# ESP32_S2_solo.net
KiCad netlist of a schematic drawn in Altium Designer
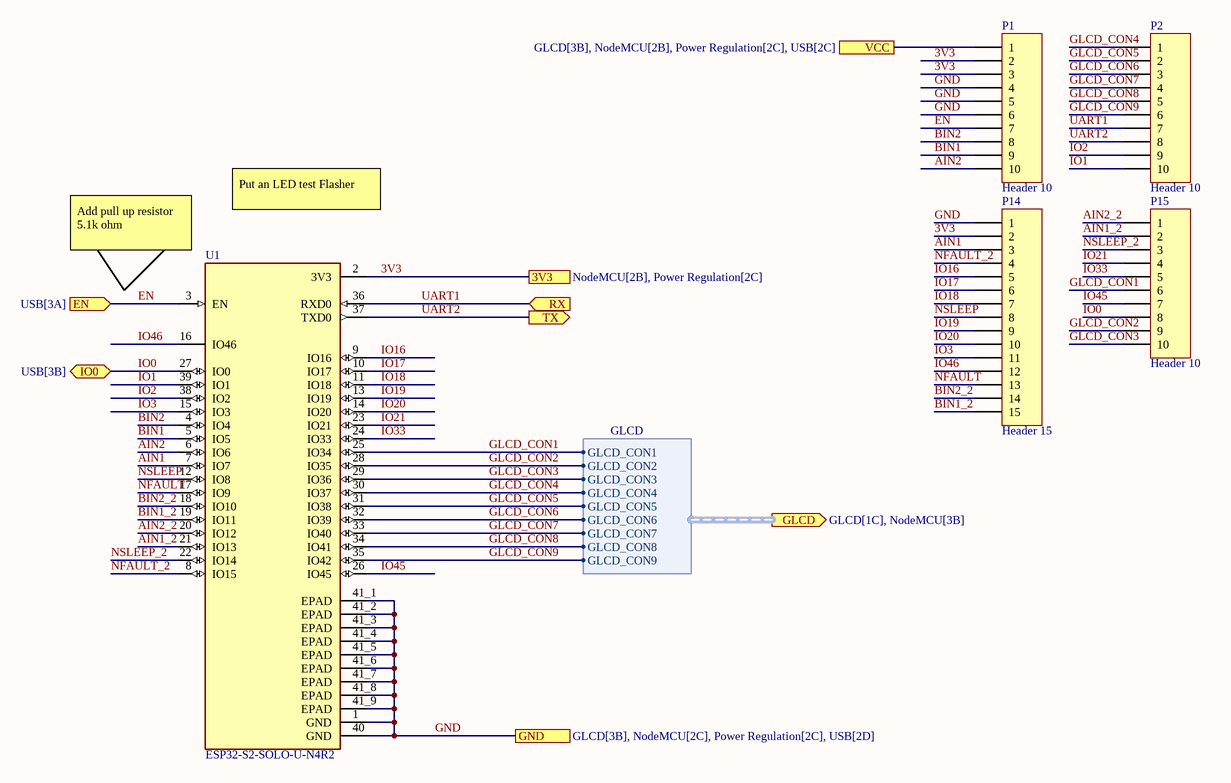
[diagram p0: ESP32_S2_solo.SchDoc]

(export (version "E")
  (design (tool "Eeschema 10.0.6"))
  (components
    (comp (ref "P1")
      (value "Header 10")
      (footprint "HDR1X10")
      (description "Header, 10-Pin")
      (fields (field (name "PUBLISHER") "Altium Limited"))
      (libsource (lib "Miscellaneous Connectors") (part "Header 10"))
    )
    (comp (ref "P2")
      (value "Header 10")
      (footprint "HDR1X10")
      (description "Header, 10-Pin")
      (fields (field (name "PUBLISHER") "Altium Limited"))
      (libsource (lib "Miscellaneous Connectors") (part "Header 10"))
    )
    (comp (ref "P14")
      (value "Header 15")
      (footprint "HDR1X15")
      (description "Header, 15-Pin")
      (fields (field (name "PUBLISHER") "Altium Limited"))
      (libsource (lib "Miscellaneous Connectors") (part "Header 15"))
    )
    (comp (ref "P15")
      (value "Header 10")
      (footprint "HDR1X10")
      (description "Header, 10-Pin")
      (fields (field (name "PUBLISHER") "Altium Limited"))
      (libsource (lib "Miscellaneous Connectors") (part "Header 10"))
    )
    (comp (ref "U1")
      (value "ESP32-S2-SOLO-U-N4R2")
      (footprint "XCVR_ESP32-S2-SOLO-U-N4R2")
      (fields (field (name "MF") "{'manufacturer': u'Espressif Systems'}"))
      (libsource (lib "SnapEDA_Library") (part "ESP32-S2-SOLO-U-N4R2"))
    )
  )
  (nets
    (net (code "2") (name "/3V3") (class "Default")
      (node (ref "P1") (pin "2") (pinfunction "2_2") (pintype "passive"))
      (node (ref "P1") (pin "3") (pinfunction "3_3") (pintype "passive"))
      (node (ref "P14") (pin "2") (pinfunction "2_2") (pintype "passive"))
      (node (ref "U1") (pin "2") (pinfunction "3V3_2") (pintype "power_in"))
    )
    (net (code "3") (name "/AIN1") (class "Default")
      (node (ref "P14") (pin "3") (pinfunction "3_3") (pintype "passive"))
      (node (ref "U1") (pin "7") (pinfunction "IO7_7") (pintype "bidirectional"))
    )
    (net (code "4") (name "/AIN1_2") (class "Default")
      (node (ref "P15") (pin "2") (pinfunction "2_2") (pintype "passive"))
      (node (ref "U1") (pin "21") (pinfunction "IO13_21") (pintype "bidirectional"))
    )
    (net (code "5") (name "/AIN2") (class "Default")
      (node (ref "P1") (pin "10") (pinfunction "10_10") (pintype "passive"))
      (node (ref "U1") (pin "6") (pinfunction "IO6_6") (pintype "bidirectional"))
    )
    (net (code "6") (name "/AIN2_2") (class "Default")
      (node (ref "P15") (pin "1") (pinfunction "1_1") (pintype "passive"))
      (node (ref "U1") (pin "20") (pinfunction "IO12_20") (pintype "bidirectional"))
    )
    (net (code "7") (name "/BIN1") (class "Default")
      (node (ref "P1") (pin "9") (pinfunction "9_9") (pintype "passive"))
      (node (ref "U1") (pin "5") (pinfunction "IO5_5") (pintype "bidirectional"))
    )
    (net (code "8") (name "/BIN1_2") (class "Default")
      (node (ref "P14") (pin "15") (pinfunction "15_15") (pintype "passive"))
      (node (ref "U1") (pin "19") (pinfunction "IO11_19") (pintype "bidirectional"))
    )
    (net (code "9") (name "/BIN2") (class "Default")
      (node (ref "P1") (pin "8") (pinfunction "8_8") (pintype "passive"))
      (node (ref "U1") (pin "4") (pinfunction "IO4_4") (pintype "bidirectional"))
    )
    (net (code "10") (name "/BIN2_2") (class "Default")
      (node (ref "P14") (pin "14") (pinfunction "14_14") (pintype "passive"))
      (node (ref "U1") (pin "18") (pinfunction "IO10_18") (pintype "bidirectional"))
    )
    (net (code "11") (name "/EN") (class "Default")
      (node (ref "P1") (pin "7") (pinfunction "7_7") (pintype "passive"))
      (node (ref "U1") (pin "3") (pinfunction "EN_3") (pintype "input"))
    )
    (net (code "12") (name "/GLCD_CON1") (class "Default")
      (node (ref "P15") (pin "6") (pinfunction "6_6") (pintype "passive"))
      (node (ref "U1") (pin "25") (pinfunction "IO34_25") (pintype "bidirectional"))
    )
    (net (code "13") (name "/GLCD_CON2") (class "Default")
      (node (ref "P15") (pin "9") (pinfunction "9_9") (pintype "passive"))
      (node (ref "U1") (pin "28") (pinfunction "IO35_28") (pintype "bidirectional"))
    )
    (net (code "14") (name "/GLCD_CON3") (class "Default")
      (node (ref "P15") (pin "10") (pinfunction "10_10") (pintype "passive"))
      (node (ref "U1") (pin "29") (pinfunction "IO36_29") (pintype "bidirectional"))
    )
    (net (code "15") (name "/GLCD_CON4") (class "Default")
      (node (ref "P2") (pin "1") (pinfunction "1_1") (pintype "passive"))
      (node (ref "U1") (pin "30") (pinfunction "IO37_30") (pintype "bidirectional"))
    )
    (net (code "16") (name "/GLCD_CON5") (class "Default")
      (node (ref "P2") (pin "2") (pinfunction "2_2") (pintype "passive"))
      (node (ref "U1") (pin "31") (pinfunction "IO38_31") (pintype "bidirectional"))
    )
    (net (code "17") (name "/GLCD_CON6") (class "Default")
      (node (ref "P2") (pin "3") (pinfunction "3_3") (pintype "passive"))
      (node (ref "U1") (pin "32") (pinfunction "IO39_32") (pintype "bidirectional"))
    )
    (net (code "18") (name "/GLCD_CON7") (class "Default")
      (node (ref "P2") (pin "4") (pinfunction "4_4") (pintype "passive"))
      (node (ref "U1") (pin "33") (pinfunction "IO40_33") (pintype "bidirectional"))
    )
    (net (code "19") (name "/GLCD_CON8") (class "Default")
      (node (ref "P2") (pin "5") (pinfunction "5_5") (pintype "passive"))
      (node (ref "U1") (pin "34") (pinfunction "IO41_34") (pintype "bidirectional"))
    )
    (net (code "20") (name "/GLCD_CON9") (class "Default")
      (node (ref "P2") (pin "6") (pinfunction "6_6") (pintype "passive"))
      (node (ref "U1") (pin "35") (pinfunction "IO42_35") (pintype "bidirectional"))
    )
    (net (code "21") (name "/GND") (class "Default")
      (node (ref "P1") (pin "4") (pinfunction "4_4") (pintype "passive"))
      (node (ref "P1") (pin "5") (pinfunction "5_5") (pintype "passive"))
      (node (ref "P1") (pin "6") (pinfunction "6_6") (pintype "passive"))
      (node (ref "P14") (pin "1") (pinfunction "1_1") (pintype "passive"))
      (node (ref "U1") (pin "1") (pinfunction "GND_1") (pintype "power_in"))
      (node (ref "U1") (pin "40") (pinfunction "GND_40") (pintype "power_in"))
      (node (ref "U1") (pin "41_1") (pinfunction "EPAD_41_1") (pintype "power_in"))
      (node (ref "U1") (pin "41_2") (pinfunction "EPAD_41_2") (pintype "power_in"))
      (node (ref "U1") (pin "41_3") (pinfunction "EPAD_41_3") (pintype "power_in"))
      (node (ref "U1") (pin "41_4") (pinfunction "EPAD_41_4") (pintype "power_in"))
      (node (ref "U1") (pin "41_5") (pinfunction "EPAD_41_5") (pintype "power_in"))
      (node (ref "U1") (pin "41_6") (pinfunction "EPAD_41_6") (pintype "power_in"))
      (node (ref "U1") (pin "41_7") (pinfunction "EPAD_41_7") (pintype "power_in"))
      (node (ref "U1") (pin "41_8") (pinfunction "EPAD_41_8") (pintype "power_in"))
      (node (ref "U1") (pin "41_9") (pinfunction "EPAD_41_9") (pintype "power_in"))
    )
    (net (code "22") (name "/IO0") (class "Default")
      (node (ref "P15") (pin "8") (pinfunction "8_8") (pintype "passive"))
      (node (ref "U1") (pin "27") (pinfunction "IO0_27") (pintype "bidirectional"))
    )
    (net (code "23") (name "/IO1") (class "Default")
      (node (ref "P2") (pin "10") (pinfunction "10_10") (pintype "passive"))
      (node (ref "U1") (pin "39") (pinfunction "IO1_39") (pintype "bidirectional"))
    )
    (net (code "24") (name "/IO2") (class "Default")
      (node (ref "P2") (pin "9") (pinfunction "9_9") (pintype "passive"))
      (node (ref "U1") (pin "38") (pinfunction "IO2_38") (pintype "bidirectional"))
    )
    (net (code "25") (name "/IO3") (class "Default")
      (node (ref "P14") (pin "11") (pinfunction "11_11") (pintype "passive"))
      (node (ref "U1") (pin "15") (pinfunction "IO3_15") (pintype "bidirectional"))
    )
    (net (code "26") (name "/IO16") (class "Default")
      (node (ref "P14") (pin "5") (pinfunction "5_5") (pintype "passive"))
      (node (ref "U1") (pin "9") (pinfunction "IO16_9") (pintype "bidirectional"))
    )
    (net (code "27") (name "/IO17") (class "Default")
      (node (ref "P14") (pin "6") (pinfunction "6_6") (pintype "passive"))
      (node (ref "U1") (pin "10") (pinfunction "IO17_10") (pintype "bidirectional"))
    )
    (net (code "28") (name "/IO18") (class "Default")
      (node (ref "P14") (pin "7") (pinfunction "7_7") (pintype "passive"))
      (node (ref "U1") (pin "11") (pinfunction "IO18_11") (pintype "bidirectional"))
    )
    (net (code "29") (name "/IO19") (class "Default")
      (node (ref "P14") (pin "9") (pinfunction "9_9") (pintype "passive"))
      (node (ref "U1") (pin "13") (pinfunction "IO19_13") (pintype "bidirectional"))
    )
    (net (code "30") (name "/IO20") (class "Default")
      (node (ref "P14") (pin "10") (pinfunction "10_10") (pintype "passive"))
      (node (ref "U1") (pin "14") (pinfunction "IO20_14") (pintype "bidirectional"))
    )
    (net (code "31") (name "/IO21") (class "Default")
      (node (ref "P15") (pin "4") (pinfunction "4_4") (pintype "passive"))
      (node (ref "U1") (pin "23") (pinfunction "IO21_23") (pintype "bidirectional"))
    )
    (net (code "32") (name "/IO33") (class "Default")
      (node (ref "P15") (pin "5") (pinfunction "5_5") (pintype "passive"))
      (node (ref "U1") (pin "24") (pinfunction "IO33_24") (pintype "bidirectional"))
    )
    (net (code "33") (name "/IO45") (class "Default")
      (node (ref "P15") (pin "7") (pinfunction "7_7") (pintype "passive"))
      (node (ref "U1") (pin "26") (pinfunction "IO45_26") (pintype "bidirectional"))
    )
    (net (code "34") (name "/IO46") (class "Default")
      (node (ref "P14") (pin "12") (pinfunction "12_12") (pintype "passive"))
      (node (ref "U1") (pin "16") (pinfunction "IO46_16") (pintype "passive"))
    )
    (net (code "35") (name "/NFAULT") (class "Default")
      (node (ref "P14") (pin "13") (pinfunction "13_13") (pintype "passive"))
      (node (ref "U1") (pin "17") (pinfunction "IO9_17") (pintype "bidirectional"))
    )
    (net (code "36") (name "/NFAULT_2") (class "Default")
      (node (ref "P14") (pin "4") (pinfunction "4_4") (pintype "passive"))
      (node (ref "U1") (pin "8") (pinfunction "IO15_8") (pintype "bidirectional"))
    )
    (net (code "37") (name "/NSLEEP") (class "Default")
      (node (ref "P14") (pin "8") (pinfunction "8_8") (pintype "passive"))
      (node (ref "U1") (pin "12") (pinfunction "IO8_12") (pintype "bidirectional"))
    )
    (net (code "38") (name "/NSLEEP_2") (class "Default")
      (node (ref "P15") (pin "3") (pinfunction "3_3") (pintype "passive"))
      (node (ref "U1") (pin "22") (pinfunction "IO14_22") (pintype "bidirectional"))
    )
    (net (code "39") (name "/UART1") (class "Default")
      (node (ref "P2") (pin "7") (pinfunction "7_7") (pintype "passive"))
      (node (ref "U1") (pin "36") (pinfunction "RXD0_36") (pintype "input"))
    )
    (net (code "40") (name "/UART2") (class "Default")
      (node (ref "P2") (pin "8") (pinfunction "8_8") (pintype "passive"))
      (node (ref "U1") (pin "37") (pinfunction "TXD0_37") (pintype "output"))
    )
    (net (code "41") (name "/VCC") (class "Default")
      (node (ref "P1") (pin "1") (pinfunction "1_1") (pintype "passive"))
    )
  )
)
